# RF-INP-001.net
KiCad netlist of a schematic drawn in EAGLE
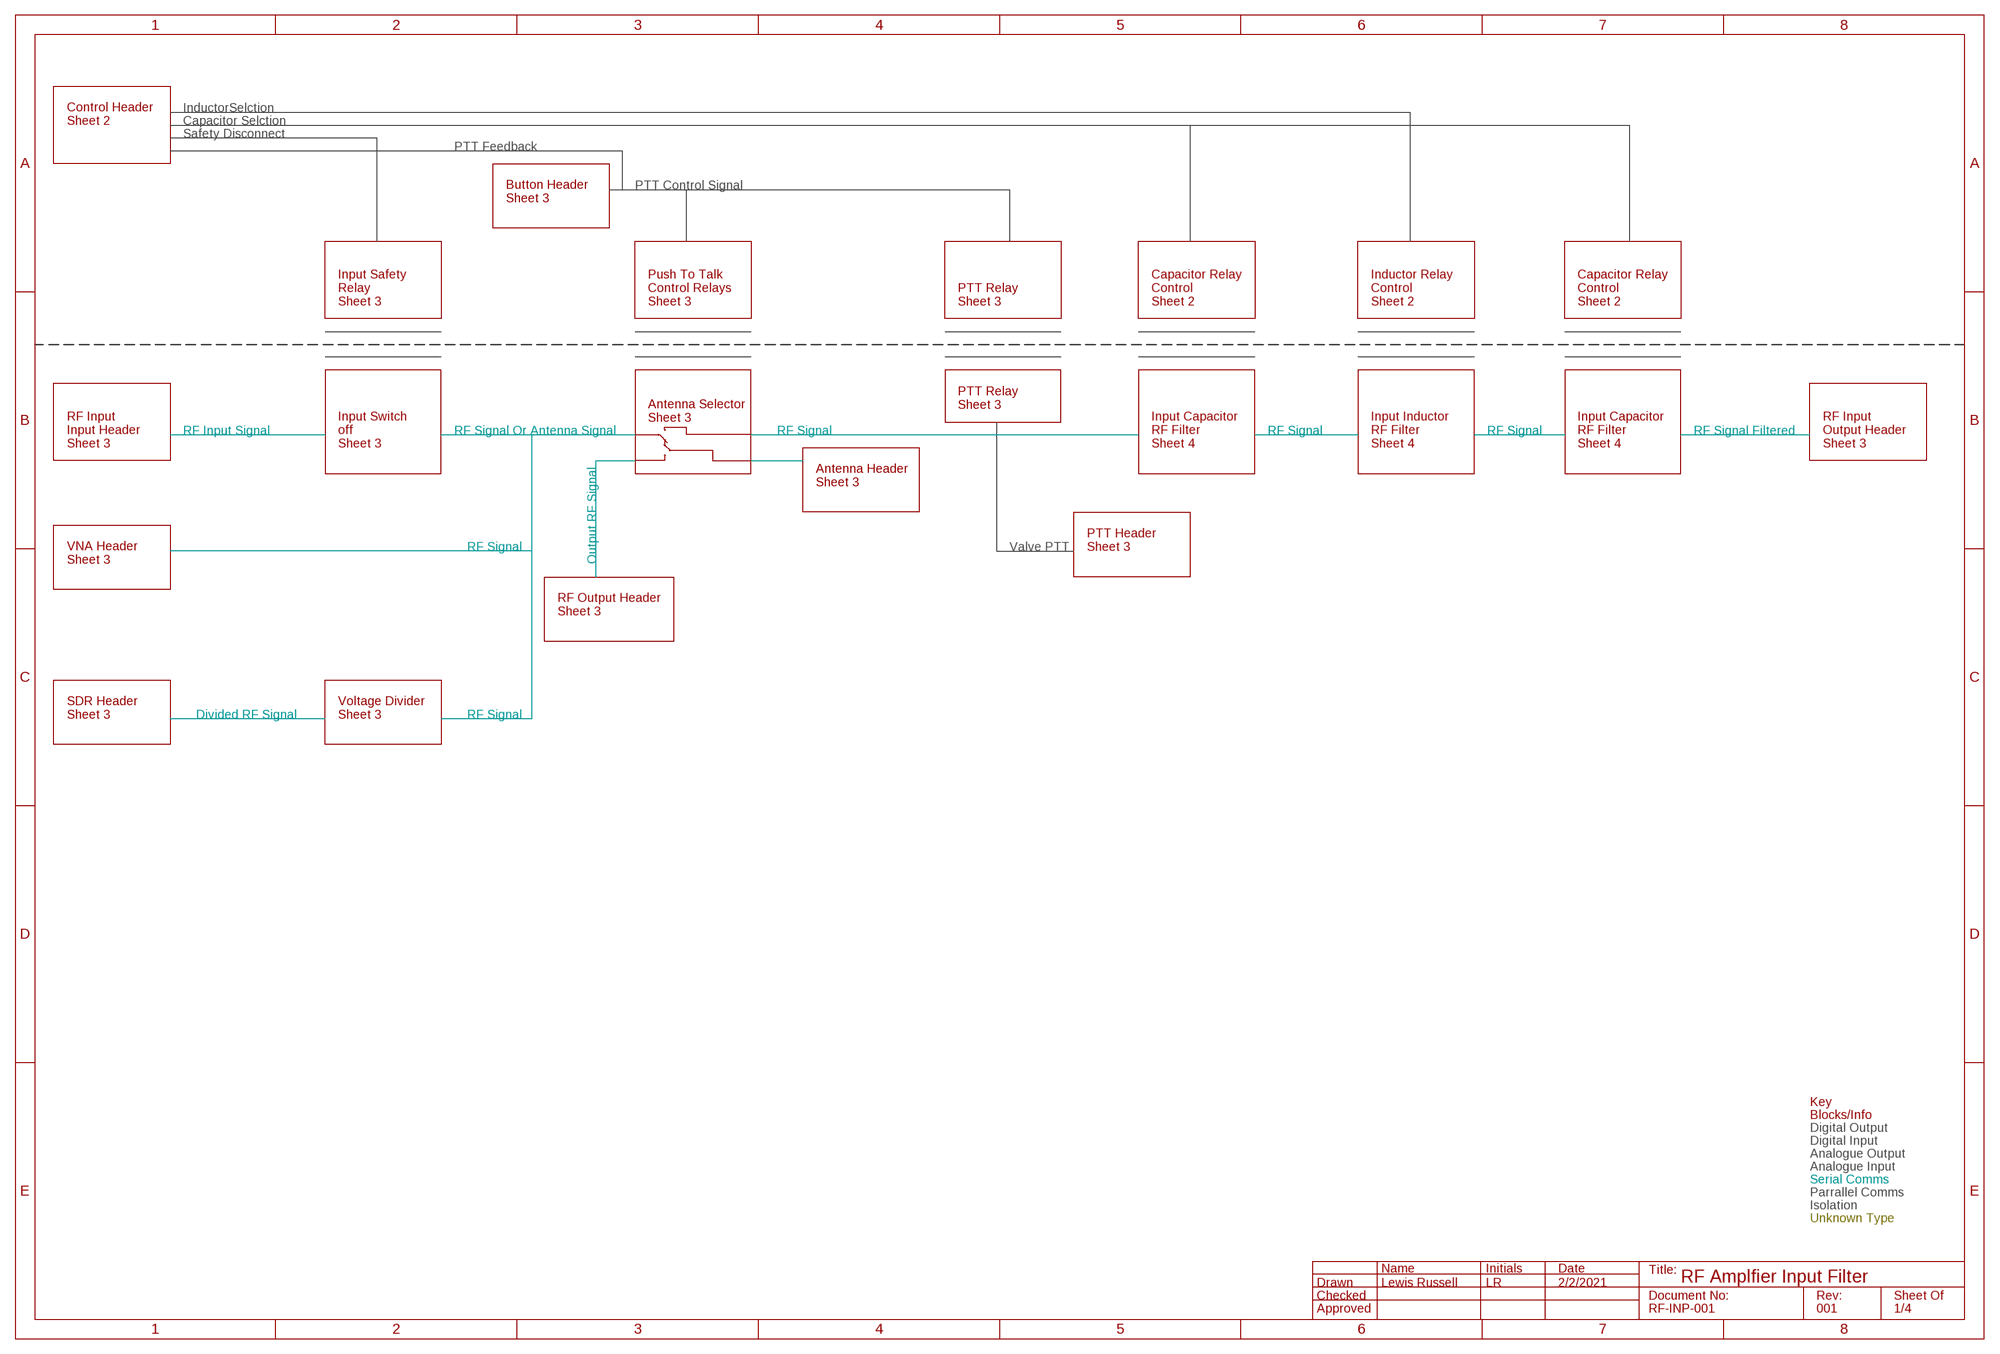
[diagram p0: schematic, sheet 1]
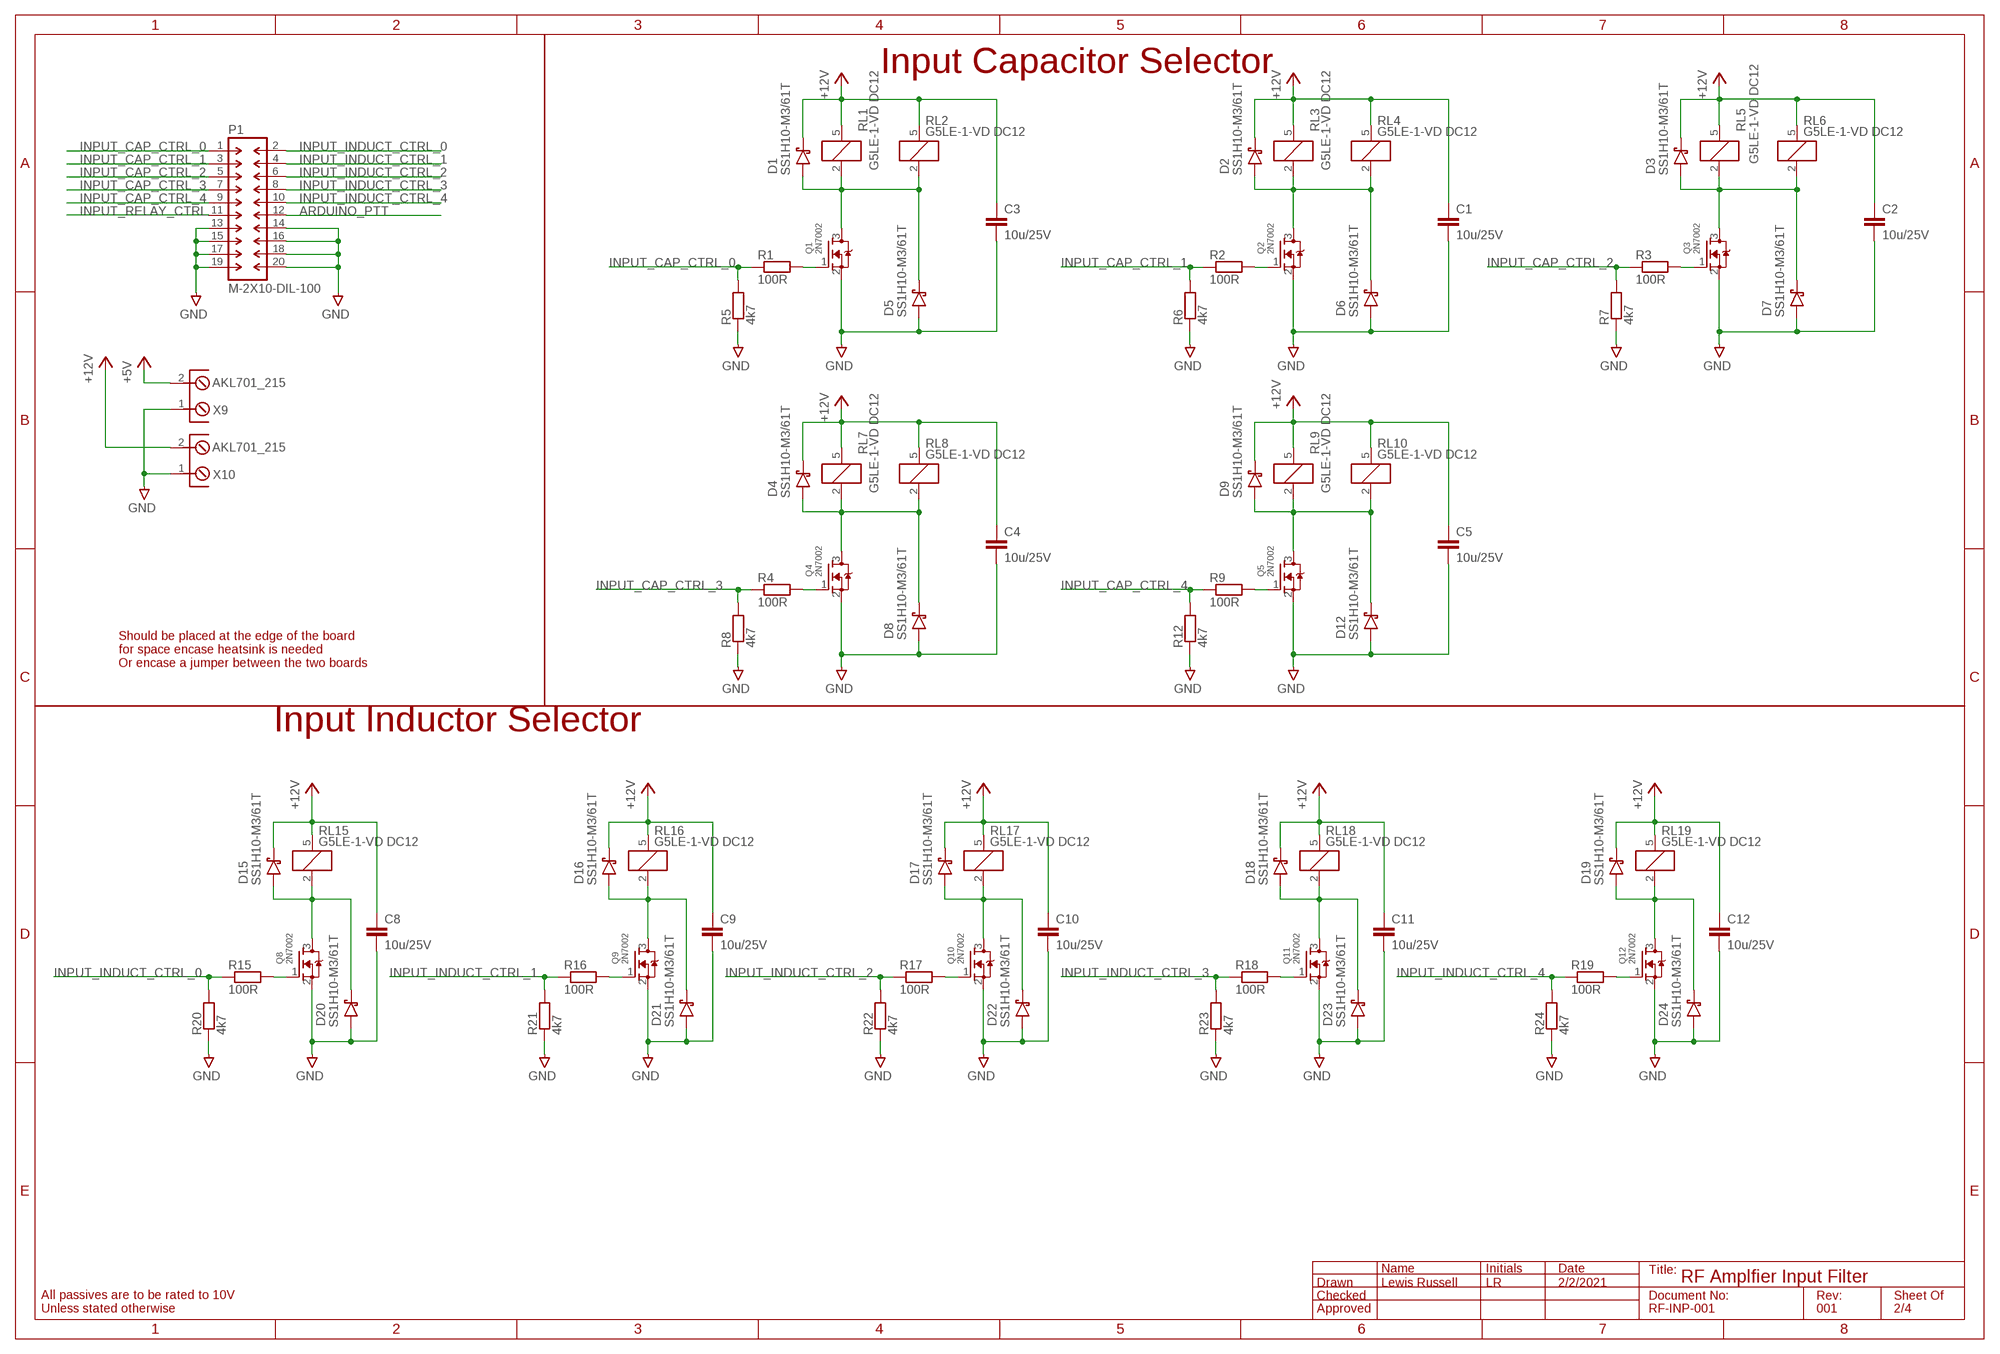
[diagram p1: schematic, sheet 2]
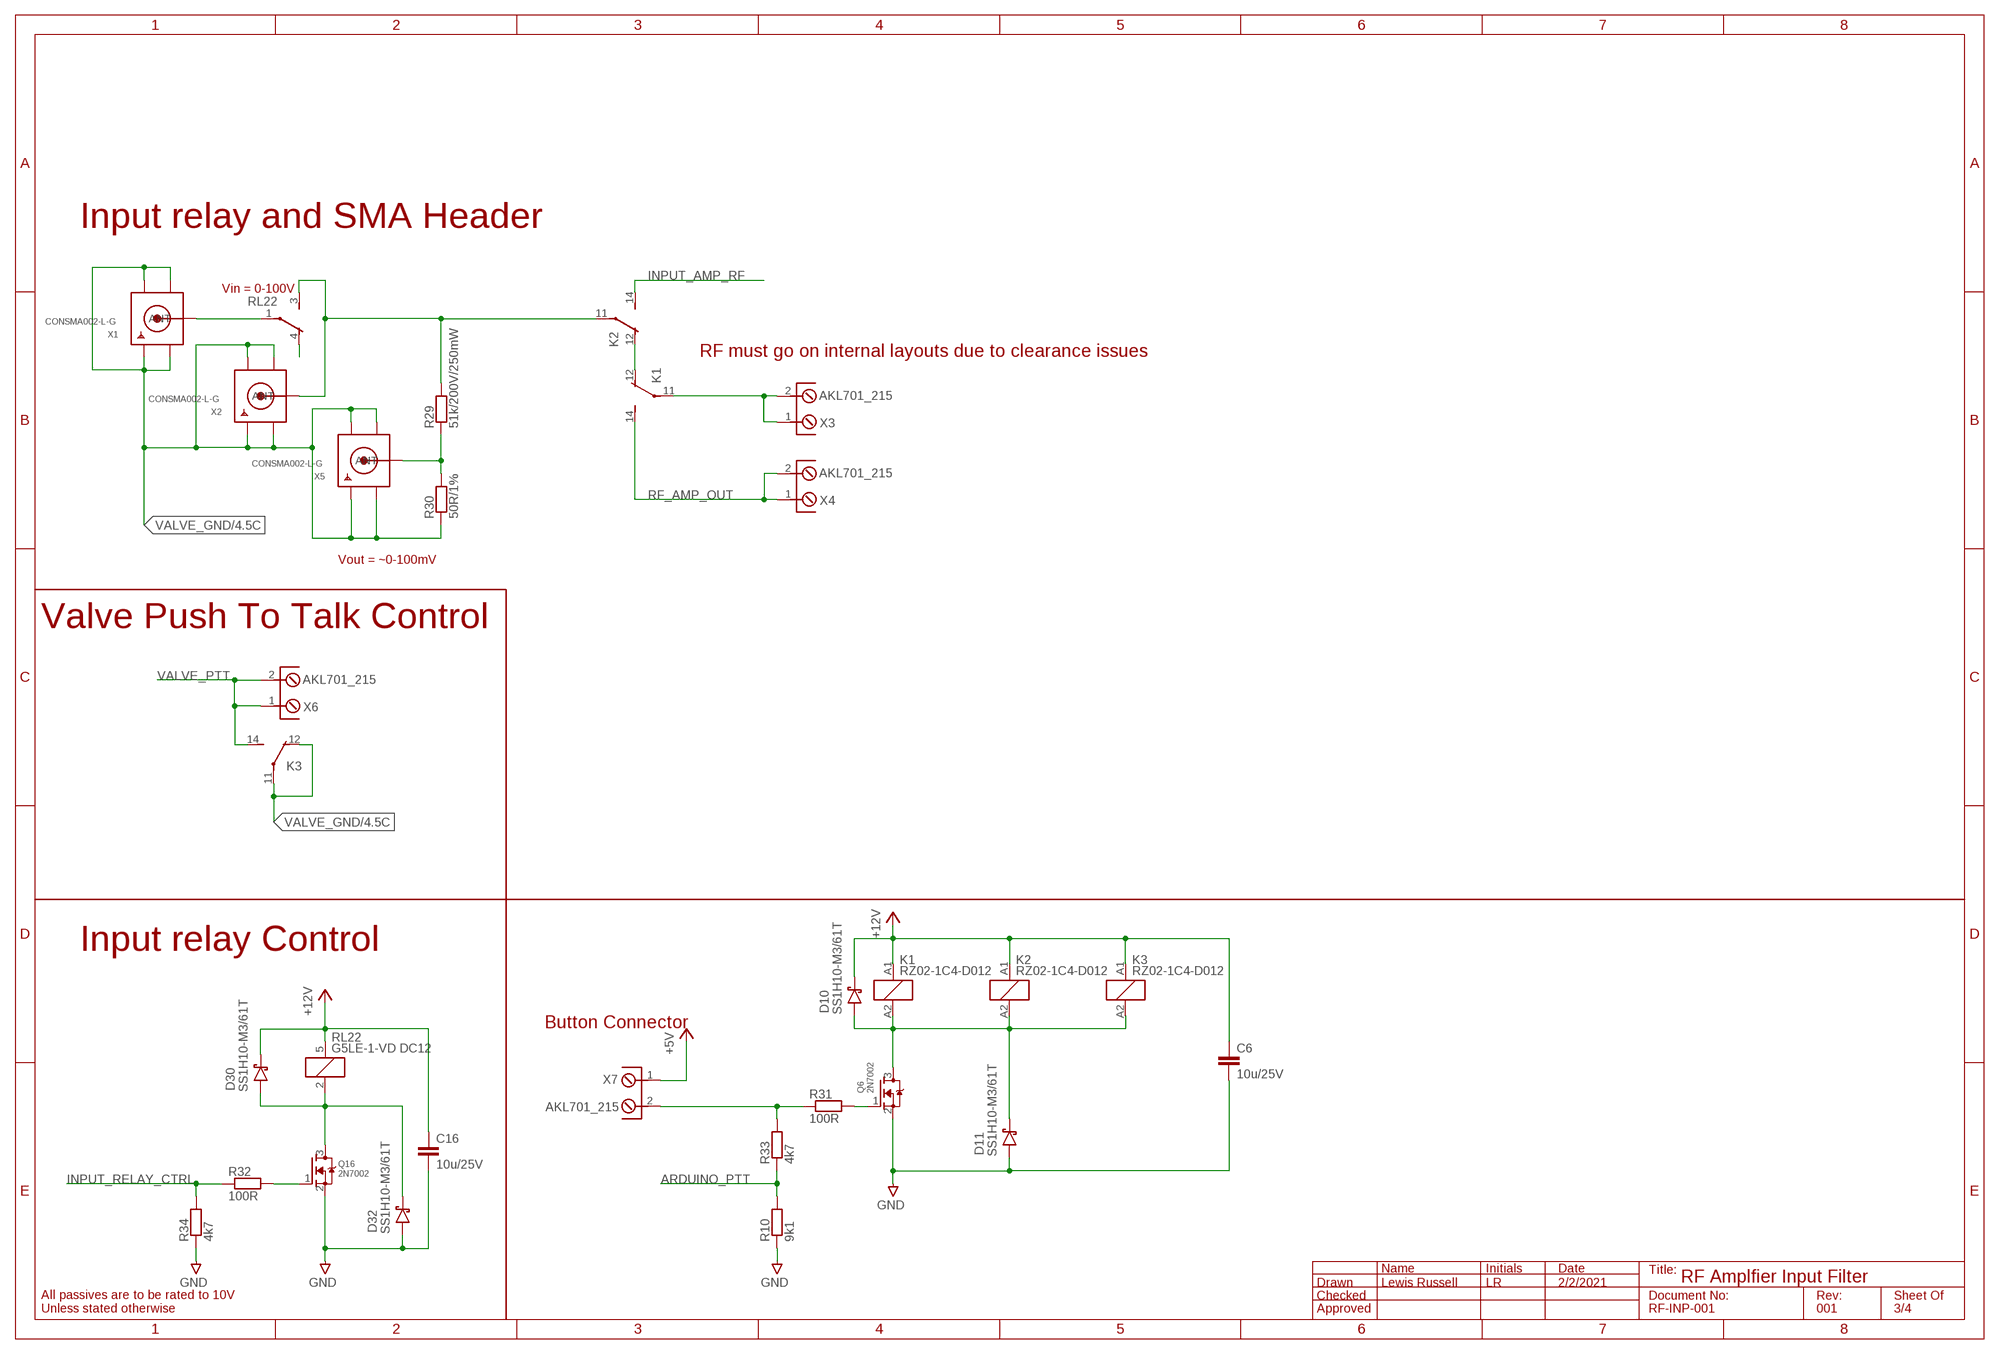
[diagram p2: schematic, sheet 3]
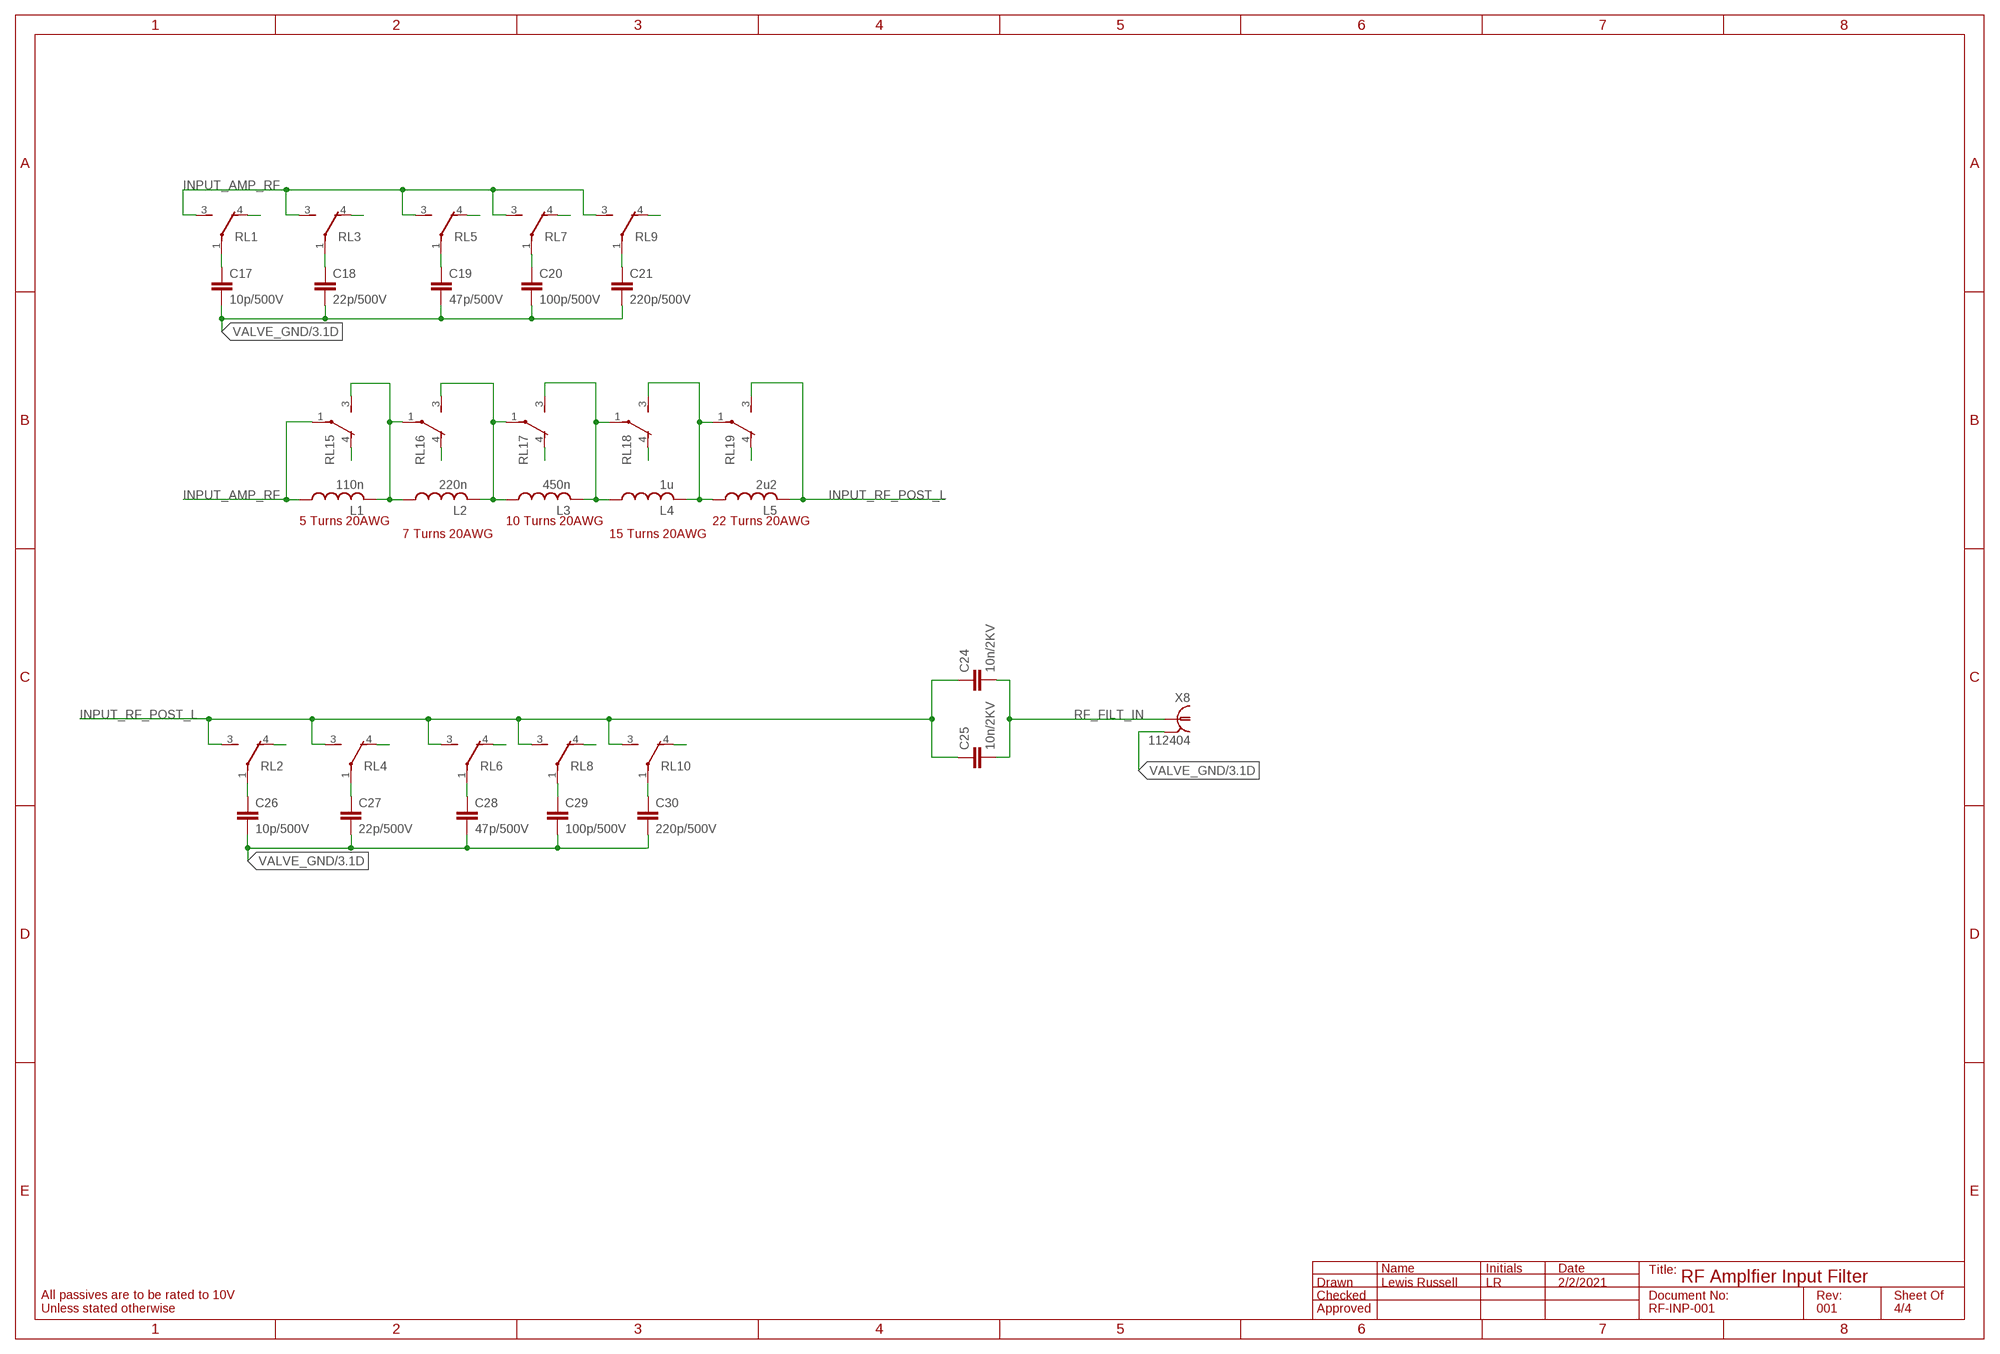
[diagram p3: schematic, sheet 4]

(export (version "E")
  (design (tool "Eeschema 10.0.6"))
  (components
    (comp (ref "C17")
      (value "10p/500V")
      (footprint "eagle-import:C1812")
      (libsource (lib "eagle-import") (part "C-EUC1812"))
    )
    (comp (ref "C18")
      (value "22p/500V")
      (footprint "eagle-import:C1812")
      (libsource (lib "eagle-import") (part "C-EUC1812"))
    )
    (comp (ref "C19")
      (value "47p/500V")
      (footprint "eagle-import:C1812")
      (libsource (lib "eagle-import") (part "C-EUC1812"))
    )
    (comp (ref "C20")
      (value "100p/500V")
      (footprint "eagle-import:C1812")
      (libsource (lib "eagle-import") (part "C-EUC1812"))
    )
    (comp (ref "C21")
      (value "220p/500V")
      (footprint "eagle-import:C1812")
      (libsource (lib "eagle-import") (part "C-EUC1812"))
    )
    (comp (ref "C24")
      (value "10n/2KV")
      (footprint "eagle-import:C1812")
      (libsource (lib "eagle-import") (part "C-EUC1812"))
    )
    (comp (ref "C25")
      (value "10n/2KV")
      (footprint "eagle-import:C1812")
      (libsource (lib "eagle-import") (part "C-EUC1812"))
    )
    (comp (ref "C26")
      (value "10p/500V")
      (footprint "eagle-import:C1812")
      (libsource (lib "eagle-import") (part "C-EUC1812"))
    )
    (comp (ref "C27")
      (value "22p/500V")
      (footprint "eagle-import:C1812")
      (libsource (lib "eagle-import") (part "C-EUC1812"))
    )
    (comp (ref "C28")
      (value "47p/500V")
      (footprint "eagle-import:C1812")
      (libsource (lib "eagle-import") (part "C-EUC1812"))
    )
    (comp (ref "C29")
      (value "100p/500V")
      (footprint "eagle-import:C1812")
      (libsource (lib "eagle-import") (part "C-EUC1812"))
    )
    (comp (ref "C30")
      (value "220p/500V")
      (footprint "eagle-import:C1812")
      (libsource (lib "eagle-import") (part "C-EUC1812"))
    )
    (comp (ref "L1")
      (value "110n")
      (footprint "eagle-import:T80-6")
      (libsource (lib "eagle-import") (part "T80-6"))
    )
    (comp (ref "L2")
      (value "220n")
      (footprint "eagle-import:T80-6")
      (libsource (lib "eagle-import") (part "T80-6"))
    )
    (comp (ref "L3")
      (value "450n")
      (footprint "eagle-import:T80-6")
      (libsource (lib "eagle-import") (part "T80-6"))
    )
    (comp (ref "L4")
      (value "1u")
      (footprint "eagle-import:T80-6")
      (libsource (lib "eagle-import") (part "T80-6"))
    )
    (comp (ref "L5")
      (value "2u2")
      (footprint "eagle-import:T80-6")
      (libsource (lib "eagle-import") (part "T80-6"))
    )
    (comp (ref "RL1")
      (value "G5LE-1-VD DC12")
      (footprint "eagle-import:SPDT")
      (libsource (lib "eagle-import") (part "G5LE-E"))
    )
    (comp (ref "RL2")
      (value "G5LE-1-VD DC12")
      (footprint "eagle-import:SPDT")
      (libsource (lib "eagle-import") (part "G5LE-E"))
    )
    (comp (ref "RL3")
      (value "G5LE-1-VD DC12")
      (footprint "eagle-import:SPDT")
      (libsource (lib "eagle-import") (part "G5LE-E"))
    )
    (comp (ref "RL4")
      (value "G5LE-1-VD DC12")
      (footprint "eagle-import:SPDT")
      (libsource (lib "eagle-import") (part "G5LE-E"))
    )
    (comp (ref "RL5")
      (value "G5LE-1-VD DC12")
      (footprint "eagle-import:SPDT")
      (libsource (lib "eagle-import") (part "G5LE-E"))
    )
    (comp (ref "RL6")
      (value "G5LE-1-VD DC12")
      (footprint "eagle-import:SPDT")
      (libsource (lib "eagle-import") (part "G5LE-E"))
    )
    (comp (ref "RL7")
      (value "G5LE-1-VD DC12")
      (footprint "eagle-import:SPDT")
      (libsource (lib "eagle-import") (part "G5LE-E"))
    )
    (comp (ref "RL8")
      (value "G5LE-1-VD DC12")
      (footprint "eagle-import:SPDT")
      (libsource (lib "eagle-import") (part "G5LE-E"))
    )
    (comp (ref "RL9")
      (value "G5LE-1-VD DC12")
      (footprint "eagle-import:SPDT")
      (libsource (lib "eagle-import") (part "G5LE-E"))
    )
    (comp (ref "RL10")
      (value "G5LE-1-VD DC12")
      (footprint "eagle-import:SPDT")
      (libsource (lib "eagle-import") (part "G5LE-E"))
    )
    (comp (ref "RL15")
      (value "G5LE-1-VD DC12")
      (footprint "eagle-import:SPDT")
      (libsource (lib "eagle-import") (part "G5LE-E"))
    )
    (comp (ref "RL16")
      (value "G5LE-1-VD DC12")
      (footprint "eagle-import:SPDT")
      (libsource (lib "eagle-import") (part "G5LE-E"))
    )
    (comp (ref "RL17")
      (value "G5LE-1-VD DC12")
      (footprint "eagle-import:SPDT")
      (libsource (lib "eagle-import") (part "G5LE-E"))
    )
    (comp (ref "RL18")
      (value "G5LE-1-VD DC12")
      (footprint "eagle-import:SPDT")
      (libsource (lib "eagle-import") (part "G5LE-E"))
    )
    (comp (ref "RL19")
      (value "G5LE-1-VD DC12")
      (footprint "eagle-import:SPDT")
      (libsource (lib "eagle-import") (part "G5LE-E"))
    )
    (comp (ref "X8")
      (value "112404")
      (footprint "eagle-import:112404")
      (fields (field (name "MF") "Amphenol Connex"))
      (libsource (lib "eagle-import") (part "112404"))
    )
    (comp (ref "C6")
      (value "10u/25V")
      (footprint "eagle-import:C0805")
      (libsource (lib "eagle-import") (part "C-EUC0805"))
    )
    (comp (ref "C16")
      (value "10u/25V")
      (footprint "eagle-import:C0805")
      (libsource (lib "eagle-import") (part "C-EUC0805"))
    )
    (comp (ref "D10")
      (value "SS1H10-M3/61T")
      (footprint "eagle-import:SMA_DO-214AC")
      (libsource (lib "eagle-import") (part "SCHOTTKY_DIODESMA"))
    )
    (comp (ref "D11")
      (value "SS1H10-M3/61T")
      (footprint "eagle-import:SMA_DO-214AC")
      (libsource (lib "eagle-import") (part "SCHOTTKY_DIODESMA"))
    )
    (comp (ref "D30")
      (value "SS1H10-M3/61T")
      (footprint "eagle-import:SMA_DO-214AC")
      (libsource (lib "eagle-import") (part "SCHOTTKY_DIODESMA"))
    )
    (comp (ref "D32")
      (value "SS1H10-M3/61T")
      (footprint "eagle-import:SMA_DO-214AC")
      (libsource (lib "eagle-import") (part "SCHOTTKY_DIODESMA"))
    )
    (comp (ref "K1")
      (value "RZ02-1C4-D012")
      (footprint "eagle-import:12A-5MM")
      (libsource (lib "eagle-import") (part "RZ02-1C"))
    )
    (comp (ref "K2")
      (value "RZ02-1C4-D012")
      (footprint "eagle-import:12A-5MM")
      (libsource (lib "eagle-import") (part "RZ02-1C"))
    )
    (comp (ref "K3")
      (value "RZ02-1C4-D012")
      (footprint "eagle-import:12A-5MM")
      (libsource (lib "eagle-import") (part "RZ02-1C"))
    )
    (comp (ref "Q6")
      (value "2N7002")
      (footprint "eagle-import:SOT23")
      (libsource (lib "eagle-import") (part "MOSFET-NREFLOW"))
    )
    (comp (ref "Q16")
      (value "2N7002")
      (footprint "eagle-import:SOT23")
      (libsource (lib "eagle-import") (part "MOSFET-NREFLOW"))
    )
    (comp (ref "R10")
      (value "9k1")
      (footprint "eagle-import:R0603")
      (libsource (lib "eagle-import") (part "R-EUR0603"))
    )
    (comp (ref "R29")
      (value "51k/200V/250mW")
      (footprint "eagle-import:R2512")
      (libsource (lib "eagle-import") (part "R-EUR2512"))
    )
    (comp (ref "R30")
      (value "50R/1%")
      (footprint "eagle-import:R0603")
      (libsource (lib "eagle-import") (part "R-EUR0603"))
    )
    (comp (ref "R31")
      (value "100R")
      (footprint "eagle-import:R0603")
      (libsource (lib "eagle-import") (part "R-EUR0603"))
    )
    (comp (ref "R32")
      (value "100R")
      (footprint "eagle-import:R0603")
      (libsource (lib "eagle-import") (part "R-EUR0603"))
    )
    (comp (ref "R33")
      (value "4k7")
      (footprint "eagle-import:R0603")
      (libsource (lib "eagle-import") (part "R-EUR0603"))
    )
    (comp (ref "R34")
      (value "4k7")
      (footprint "eagle-import:R0603")
      (libsource (lib "eagle-import") (part "R-EUR0603"))
    )
    (comp (ref "RL22")
      (value "G5LE-1-VD DC12")
      (footprint "eagle-import:SPDT")
      (libsource (lib "eagle-import") (part "G5LE-E"))
    )
    (comp (ref "X1")
      (value "CONSMA002-L-G")
      (footprint "eagle-import:SMA90_DIP")
      (libsource (lib "eagle-import") (part "SMACONNECTOR"))
    )
    (comp (ref "X2")
      (value "CONSMA002-L-G")
      (footprint "eagle-import:SMA90_DIP")
      (libsource (lib "eagle-import") (part "SMACONNECTOR"))
    )
    (comp (ref "X3")
      (value "AKL701_215")
      (footprint "eagle-import:AKL701_2_15")
      (libsource (lib "eagle-import") (part "AKL701_215"))
    )
    (comp (ref "X4")
      (value "AKL701_215")
      (footprint "eagle-import:AKL701_2_15")
      (libsource (lib "eagle-import") (part "AKL701_215"))
    )
    (comp (ref "X5")
      (value "CONSMA002-L-G")
      (footprint "eagle-import:SMA90_DIP")
      (libsource (lib "eagle-import") (part "SMACONNECTOR"))
    )
    (comp (ref "X6")
      (value "AKL701_215")
      (footprint "eagle-import:AKL701_2_15")
      (libsource (lib "eagle-import") (part "AKL701_215"))
    )
    (comp (ref "X7")
      (value "AKL701_215")
      (footprint "eagle-import:AKL701_2_15")
      (libsource (lib "eagle-import") (part "AKL701_215"))
    )
    (comp (ref "C1")
      (value "10u/25V")
      (footprint "eagle-import:C0805")
      (libsource (lib "eagle-import") (part "C-EUC0805"))
    )
    (comp (ref "C2")
      (value "10u/25V")
      (footprint "eagle-import:C0805")
      (libsource (lib "eagle-import") (part "C-EUC0805"))
    )
    (comp (ref "C3")
      (value "10u/25V")
      (footprint "eagle-import:C0805")
      (libsource (lib "eagle-import") (part "C-EUC0805"))
    )
    (comp (ref "C4")
      (value "10u/25V")
      (footprint "eagle-import:C0805")
      (libsource (lib "eagle-import") (part "C-EUC0805"))
    )
    (comp (ref "C5")
      (value "10u/25V")
      (footprint "eagle-import:C0805")
      (libsource (lib "eagle-import") (part "C-EUC0805"))
    )
    (comp (ref "C8")
      (value "10u/25V")
      (footprint "eagle-import:C0805")
      (libsource (lib "eagle-import") (part "C-EUC0805"))
    )
    (comp (ref "C9")
      (value "10u/25V")
      (footprint "eagle-import:C0805")
      (libsource (lib "eagle-import") (part "C-EUC0805"))
    )
    (comp (ref "C10")
      (value "10u/25V")
      (footprint "eagle-import:C0805")
      (libsource (lib "eagle-import") (part "C-EUC0805"))
    )
    (comp (ref "C11")
      (value "10u/25V")
      (footprint "eagle-import:C0805")
      (libsource (lib "eagle-import") (part "C-EUC0805"))
    )
    (comp (ref "C12")
      (value "10u/25V")
      (footprint "eagle-import:C0805")
      (libsource (lib "eagle-import") (part "C-EUC0805"))
    )
    (comp (ref "D1")
      (value "SS1H10-M3/61T")
      (footprint "eagle-import:SMA_DO-214AC")
      (libsource (lib "eagle-import") (part "SCHOTTKY_DIODESMA"))
    )
    (comp (ref "D2")
      (value "SS1H10-M3/61T")
      (footprint "eagle-import:SMA_DO-214AC")
      (libsource (lib "eagle-import") (part "SCHOTTKY_DIODESMA"))
    )
    (comp (ref "D3")
      (value "SS1H10-M3/61T")
      (footprint "eagle-import:SMA_DO-214AC")
      (libsource (lib "eagle-import") (part "SCHOTTKY_DIODESMA"))
    )
    (comp (ref "D4")
      (value "SS1H10-M3/61T")
      (footprint "eagle-import:SMA_DO-214AC")
      (libsource (lib "eagle-import") (part "SCHOTTKY_DIODESMA"))
    )
    (comp (ref "D5")
      (value "SS1H10-M3/61T")
      (footprint "eagle-import:SMA_DO-214AC")
      (libsource (lib "eagle-import") (part "SCHOTTKY_DIODESMA"))
    )
    (comp (ref "D6")
      (value "SS1H10-M3/61T")
      (footprint "eagle-import:SMA_DO-214AC")
      (libsource (lib "eagle-import") (part "SCHOTTKY_DIODESMA"))
    )
    (comp (ref "D7")
      (value "SS1H10-M3/61T")
      (footprint "eagle-import:SMA_DO-214AC")
      (libsource (lib "eagle-import") (part "SCHOTTKY_DIODESMA"))
    )
    (comp (ref "D8")
      (value "SS1H10-M3/61T")
      (footprint "eagle-import:SMA_DO-214AC")
      (libsource (lib "eagle-import") (part "SCHOTTKY_DIODESMA"))
    )
    (comp (ref "D9")
      (value "SS1H10-M3/61T")
      (footprint "eagle-import:SMA_DO-214AC")
      (libsource (lib "eagle-import") (part "SCHOTTKY_DIODESMA"))
    )
    (comp (ref "D12")
      (value "SS1H10-M3/61T")
      (footprint "eagle-import:SMA_DO-214AC")
      (libsource (lib "eagle-import") (part "SCHOTTKY_DIODESMA"))
    )
    (comp (ref "D15")
      (value "SS1H10-M3/61T")
      (footprint "eagle-import:SMA_DO-214AC")
      (libsource (lib "eagle-import") (part "SCHOTTKY_DIODESMA"))
    )
    (comp (ref "D16")
      (value "SS1H10-M3/61T")
      (footprint "eagle-import:SMA_DO-214AC")
      (libsource (lib "eagle-import") (part "SCHOTTKY_DIODESMA"))
    )
    (comp (ref "D17")
      (value "SS1H10-M3/61T")
      (footprint "eagle-import:SMA_DO-214AC")
      (libsource (lib "eagle-import") (part "SCHOTTKY_DIODESMA"))
    )
    (comp (ref "D18")
      (value "SS1H10-M3/61T")
      (footprint "eagle-import:SMA_DO-214AC")
      (libsource (lib "eagle-import") (part "SCHOTTKY_DIODESMA"))
    )
    (comp (ref "D19")
      (value "SS1H10-M3/61T")
      (footprint "eagle-import:SMA_DO-214AC")
      (libsource (lib "eagle-import") (part "SCHOTTKY_DIODESMA"))
    )
    (comp (ref "D20")
      (value "SS1H10-M3/61T")
      (footprint "eagle-import:SMA_DO-214AC")
      (libsource (lib "eagle-import") (part "SCHOTTKY_DIODESMA"))
    )
    (comp (ref "D21")
      (value "SS1H10-M3/61T")
      (footprint "eagle-import:SMA_DO-214AC")
      (libsource (lib "eagle-import") (part "SCHOTTKY_DIODESMA"))
    )
    (comp (ref "D22")
      (value "SS1H10-M3/61T")
      (footprint "eagle-import:SMA_DO-214AC")
      (libsource (lib "eagle-import") (part "SCHOTTKY_DIODESMA"))
    )
    (comp (ref "D23")
      (value "SS1H10-M3/61T")
      (footprint "eagle-import:SMA_DO-214AC")
      (libsource (lib "eagle-import") (part "SCHOTTKY_DIODESMA"))
    )
    (comp (ref "D24")
      (value "SS1H10-M3/61T")
      (footprint "eagle-import:SMA_DO-214AC")
      (libsource (lib "eagle-import") (part "SCHOTTKY_DIODESMA"))
    )
    (comp (ref "P1")
      (value "M-2X10-DIL-100")
      (footprint "eagle-import:DIL-100-2X10")
      (libsource (lib "eagle-import") (part "M-2X10-DIL-100"))
    )
    (comp (ref "Q1")
      (value "2N7002")
      (footprint "eagle-import:SOT23")
      (libsource (lib "eagle-import") (part "MOSFET-NREFLOW"))
    )
    (comp (ref "Q2")
      (value "2N7002")
      (footprint "eagle-import:SOT23")
      (libsource (lib "eagle-import") (part "MOSFET-NREFLOW"))
    )
    (comp (ref "Q3")
      (value "2N7002")
      (footprint "eagle-import:SOT23")
      (libsource (lib "eagle-import") (part "MOSFET-NREFLOW"))
    )
    (comp (ref "Q4")
      (value "2N7002")
      (footprint "eagle-import:SOT23")
      (libsource (lib "eagle-import") (part "MOSFET-NREFLOW"))
    )
    (comp (ref "Q5")
      (value "2N7002")
      (footprint "eagle-import:SOT23")
      (libsource (lib "eagle-import") (part "MOSFET-NREFLOW"))
    )
    (comp (ref "Q8")
      (value "2N7002")
      (footprint "eagle-import:SOT23")
      (libsource (lib "eagle-import") (part "MOSFET-NREFLOW"))
    )
    (comp (ref "Q9")
      (value "2N7002")
      (footprint "eagle-import:SOT23")
      (libsource (lib "eagle-import") (part "MOSFET-NREFLOW"))
    )
    (comp (ref "Q10")
      (value "2N7002")
      (footprint "eagle-import:SOT23")
      (libsource (lib "eagle-import") (part "MOSFET-NREFLOW"))
    )
    (comp (ref "Q11")
      (value "2N7002")
      (footprint "eagle-import:SOT23")
      (libsource (lib "eagle-import") (part "MOSFET-NREFLOW"))
    )
    (comp (ref "Q12")
      (value "2N7002")
      (footprint "eagle-import:SOT23")
      (libsource (lib "eagle-import") (part "MOSFET-NREFLOW"))
    )
    (comp (ref "R1")
      (value "100R")
      (footprint "eagle-import:R0603")
      (libsource (lib "eagle-import") (part "R-EUR0603"))
    )
    (comp (ref "R2")
      (value "100R")
      (footprint "eagle-import:R0603")
      (libsource (lib "eagle-import") (part "R-EUR0603"))
    )
    (comp (ref "R3")
      (value "100R")
      (footprint "eagle-import:R0603")
      (libsource (lib "eagle-import") (part "R-EUR0603"))
    )
    (comp (ref "R4")
      (value "100R")
      (footprint "eagle-import:R0603")
      (libsource (lib "eagle-import") (part "R-EUR0603"))
    )
    (comp (ref "R5")
      (value "4k7")
      (footprint "eagle-import:R0603")
      (libsource (lib "eagle-import") (part "R-EUR0603"))
    )
    (comp (ref "R6")
      (value "4k7")
      (footprint "eagle-import:R0603")
      (libsource (lib "eagle-import") (part "R-EUR0603"))
    )
    (comp (ref "R7")
      (value "4k7")
      (footprint "eagle-import:R0603")
      (libsource (lib "eagle-import") (part "R-EUR0603"))
    )
    (comp (ref "R8")
      (value "4k7")
      (footprint "eagle-import:R0603")
      (libsource (lib "eagle-import") (part "R-EUR0603"))
    )
    (comp (ref "R9")
      (value "100R")
      (footprint "eagle-import:R0603")
      (libsource (lib "eagle-import") (part "R-EUR0603"))
    )
    (comp (ref "R12")
      (value "4k7")
      (footprint "eagle-import:R0603")
      (libsource (lib "eagle-import") (part "R-EUR0603"))
    )
    (comp (ref "R15")
      (value "100R")
      (footprint "eagle-import:R0603")
      (libsource (lib "eagle-import") (part "R-EUR0603"))
    )
    (comp (ref "R16")
      (value "100R")
      (footprint "eagle-import:R0603")
      (libsource (lib "eagle-import") (part "R-EUR0603"))
    )
    (comp (ref "R17")
      (value "100R")
      (footprint "eagle-import:R0603")
      (libsource (lib "eagle-import") (part "R-EUR0603"))
    )
    (comp (ref "R18")
      (value "100R")
      (footprint "eagle-import:R0603")
      (libsource (lib "eagle-import") (part "R-EUR0603"))
    )
    (comp (ref "R19")
      (value "100R")
      (footprint "eagle-import:R0603")
      (libsource (lib "eagle-import") (part "R-EUR0603"))
    )
    (comp (ref "R20")
      (value "4k7")
      (footprint "eagle-import:R0603")
      (libsource (lib "eagle-import") (part "R-EUR0603"))
    )
    (comp (ref "R21")
      (value "4k7")
      (footprint "eagle-import:R0603")
      (libsource (lib "eagle-import") (part "R-EUR0603"))
    )
    (comp (ref "R22")
      (value "4k7")
      (footprint "eagle-import:R0603")
      (libsource (lib "eagle-import") (part "R-EUR0603"))
    )
    (comp (ref "R23")
      (value "4k7")
      (footprint "eagle-import:R0603")
      (libsource (lib "eagle-import") (part "R-EUR0603"))
    )
    (comp (ref "R24")
      (value "4k7")
      (footprint "eagle-import:R0603")
      (libsource (lib "eagle-import") (part "R-EUR0603"))
    )
    (comp (ref "X9")
      (value "AKL701_215")
      (footprint "eagle-import:AKL701_2_15")
      (libsource (lib "eagle-import") (part "AKL701_215"))
    )
    (comp (ref "X10")
      (value "AKL701_215")
      (footprint "eagle-import:AKL701_2_15")
      (libsource (lib "eagle-import") (part "AKL701_215"))
    )
  )
  (nets
    (net (code "1") (name "+5V") (class "Default")
      (node (ref "X7") (pin "1") (pinfunction "1_1") (pintype "passive"))
      (node (ref "X9") (pin "2") (pinfunction "2_2") (pintype "passive"))
    )
    (net (code "2") (name "+12V") (class "Default")
      (node (ref "C1") (pin "1") (pinfunction "1_1") (pintype "passive"))
      (node (ref "C10") (pin "1") (pinfunction "1_1") (pintype "passive"))
      (node (ref "C11") (pin "1") (pinfunction "1_1") (pintype "passive"))
      (node (ref "C12") (pin "1") (pinfunction "1_1") (pintype "passive"))
      (node (ref "C16") (pin "1") (pinfunction "1_1") (pintype "passive"))
      (node (ref "C2") (pin "1") (pinfunction "1_1") (pintype "passive"))
      (node (ref "C3") (pin "1") (pinfunction "1_1") (pintype "passive"))
      (node (ref "C4") (pin "1") (pinfunction "1_1") (pintype "passive"))
      (node (ref "C5") (pin "1") (pinfunction "1_1") (pintype "passive"))
      (node (ref "C6") (pin "1") (pinfunction "1_1") (pintype "passive"))
      (node (ref "C8") (pin "1") (pinfunction "1_1") (pintype "passive"))
      (node (ref "C9") (pin "1") (pinfunction "1_1") (pintype "passive"))
      (node (ref "D1") (pin "C") (pinfunction "CATHODE_C") (pintype "bidirectional"))
      (node (ref "D10") (pin "C") (pinfunction "CATHODE_C") (pintype "bidirectional"))
      (node (ref "D15") (pin "C") (pinfunction "CATHODE_C") (pintype "bidirectional"))
      (node (ref "D16") (pin "C") (pinfunction "CATHODE_C") (pintype "bidirectional"))
      (node (ref "D17") (pin "C") (pinfunction "CATHODE_C") (pintype "bidirectional"))
      (node (ref "D18") (pin "C") (pinfunction "CATHODE_C") (pintype "bidirectional"))
      (node (ref "D19") (pin "C") (pinfunction "CATHODE_C") (pintype "bidirectional"))
      (node (ref "D2") (pin "C") (pinfunction "CATHODE_C") (pintype "bidirectional"))
      (node (ref "D3") (pin "C") (pinfunction "CATHODE_C") (pintype "bidirectional"))
      (node (ref "D30") (pin "C") (pinfunction "CATHODE_C") (pintype "bidirectional"))
      (node (ref "D4") (pin "C") (pinfunction "CATHODE_C") (pintype "bidirectional"))
      (node (ref "D9") (pin "C") (pinfunction "CATHODE_C") (pintype "bidirectional"))
      (node (ref "K1") (pin "A1") (pinfunction "1_A1") (pintype "passive"))
      (node (ref "K2") (pin "A1") (pinfunction "1_A1") (pintype "passive"))
      (node (ref "K3") (pin "A1") (pinfunction "1_A1") (pintype "passive"))
      (node (ref "RL1") (pin "5") (pinfunction "5_5") (pintype "passive"))
      (node (ref "RL10") (pin "5") (pinfunction "5_5") (pintype "passive"))
      (node (ref "RL15") (pin "5") (pinfunction "5_5") (pintype "passive"))
      (node (ref "RL16") (pin "5") (pinfunction "5_5") (pintype "passive"))
      (node (ref "RL17") (pin "5") (pinfunction "5_5") (pintype "passive"))
      (node (ref "RL18") (pin "5") (pinfunction "5_5") (pintype "passive"))
      (node (ref "RL19") (pin "5") (pinfunction "5_5") (pintype "passive"))
      (node (ref "RL2") (pin "5") (pinfunction "5_5") (pintype "passive"))
      (node (ref "RL22") (pin "5") (pinfunction "5_5") (pintype "passive"))
      (node (ref "RL3") (pin "5") (pinfunction "5_5") (pintype "passive"))
      (node (ref "RL4") (pin "5") (pinfunction "5_5") (pintype "passive"))
      (node (ref "RL5") (pin "5") (pinfunction "5_5") (pintype "passive"))
      (node (ref "RL6") (pin "5") (pinfunction "5_5") (pintype "passive"))
      (node (ref "RL7") (pin "5") (pinfunction "5_5") (pintype "passive"))
      (node (ref "RL8") (pin "5") (pinfunction "5_5") (pintype "passive"))
      (node (ref "RL9") (pin "5") (pinfunction "5_5") (pintype "passive"))
      (node (ref "X10") (pin "2") (pinfunction "2_2") (pintype "passive"))
    )
    (net (code "3") (name "ARDUINO_PTT") (class "Default")
      (node (ref "P1") (pin "12") (pinfunction "12_12") (pintype "passive"))
      (node (ref "R10") (pin "2") (pinfunction "2_2") (pintype "passive"))
      (node (ref "R33") (pin "1") (pinfunction "1_1") (pintype "passive"))
    )
    (net (code "4") (name "GND") (class "Default")
      (node (ref "C1") (pin "2") (pinfunction "2_2") (pintype "passive"))
      (node (ref "C10") (pin "2") (pinfunction "2_2") (pintype "passive"))
      (node (ref "C11") (pin "2") (pinfunction "2_2") (pintype "passive"))
      (node (ref "C12") (pin "2") (pinfunction "2_2") (pintype "passive"))
      (node (ref "C16") (pin "2") (pinfunction "2_2") (pintype "passive"))
      (node (ref "C2") (pin "2") (pinfunction "2_2") (pintype "passive"))
      (node (ref "C3") (pin "2") (pinfunction "2_2") (pintype "passive"))
      (node (ref "C4") (pin "2") (pinfunction "2_2") (pintype "passive"))
      (node (ref "C5") (pin "2") (pinfunction "2_2") (pintype "passive"))
      (node (ref "C6") (pin "2") (pinfunction "2_2") (pintype "passive"))
      (node (ref "C8") (pin "2") (pinfunction "2_2") (pintype "passive"))
      (node (ref "C9") (pin "2") (pinfunction "2_2") (pintype "passive"))
      (node (ref "D11") (pin "A") (pinfunction "ANODE_A") (pintype "bidirectional"))
      (node (ref "D12") (pin "A") (pinfunction "ANODE_A") (pintype "bidirectional"))
      (node (ref "D20") (pin "A") (pinfunction "ANODE_A") (pintype "bidirectional"))
      (node (ref "D21") (pin "A") (pinfunction "ANODE_A") (pintype "bidirectional"))
      (node (ref "D22") (pin "A") (pinfunction "ANODE_A") (pintype "bidirectional"))
      (node (ref "D23") (pin "A") (pinfunction "ANODE_A") (pintype "bidirectional"))
      (node (ref "D24") (pin "A") (pinfunction "ANODE_A") (pintype "bidirectional"))
      (node (ref "D32") (pin "A") (pinfunction "ANODE_A") (pintype "bidirectional"))
      (node (ref "D5") (pin "A") (pinfunction "ANODE_A") (pintype "bidirectional"))
      (node (ref "D6") (pin "A") (pinfunction "ANODE_A") (pintype "bidirectional"))
      (node (ref "D7") (pin "A") (pinfunction "ANODE_A") (pintype "bidirectional"))
      (node (ref "D8") (pin "A") (pinfunction "ANODE_A") (pintype "bidirectional"))
      (node (ref "P1") (pin "13") (pinfunction "13_13") (pintype "passive"))
      (node (ref "P1") (pin "14") (pinfunction "14_14") (pintype "passive"))
      (node (ref "P1") (pin "15") (pinfunction "15_15") (pintype "passive"))
      (node (ref "P1") (pin "16") (pinfunction "16_16") (pintype "passive"))
      (node (ref "P1") (pin "17") (pinfunction "17_17") (pintype "passive"))
      (node (ref "P1") (pin "18") (pinfunction "18_18") (pintype "passive"))
      (node (ref "P1") (pin "19") (pinfunction "19_19") (pintype "passive"))
      (node (ref "P1") (pin "20") (pinfunction "20_20") (pintype "passive"))
      (node (ref "Q1") (pin "2") (pinfunction "S_2") (pintype "bidirectional"))
      (node (ref "Q10") (pin "2") (pinfunction "S_2") (pintype "bidirectional"))
      (node (ref "Q11") (pin "2") (pinfunction "S_2") (pintype "bidirectional"))
      (node (ref "Q12") (pin "2") (pinfunction "S_2") (pintype "bidirectional"))
      (node (ref "Q16") (pin "2") (pinfunction "S_2") (pintype "bidirectional"))
      (node (ref "Q2") (pin "2") (pinfunction "S_2") (pintype "bidirectional"))
      (node (ref "Q3") (pin "2") (pinfunction "S_2") (pintype "bidirectional"))
      (node (ref "Q4") (pin "2") (pinfunction "S_2") (pintype "bidirectional"))
      (node (ref "Q5") (pin "2") (pinfunction "S_2") (pintype "bidirectional"))
      (node (ref "Q6") (pin "2") (pinfunction "S_2") (pintype "bidirectional"))
      (node (ref "Q8") (pin "2") (pinfunction "S_2") (pintype "bidirectional"))
      (node (ref "Q9") (pin "2") (pinfunction "S_2") (pintype "bidirectional"))
      (node (ref "R10") (pin "1") (pinfunction "1_1") (pintype "passive"))
      (node (ref "R12") (pin "1") (pinfunction "1_1") (pintype "passive"))
      (node (ref "R20") (pin "1") (pinfunction "1_1") (pintype "passive"))
      (node (ref "R21") (pin "1") (pinfunction "1_1") (pintype "passive"))
      (node (ref "R22") (pin "1") (pinfunction "1_1") (pintype "passive"))
      (node (ref "R23") (pin "1") (pinfunction "1_1") (pintype "passive"))
      (node (ref "R24") (pin "1") (pinfunction "1_1") (pintype "passive"))
      (node (ref "R34") (pin "1") (pinfunction "1_1") (pintype "passive"))
      (node (ref "R5") (pin "1") (pinfunction "1_1") (pintype "passive"))
      (node (ref "R6") (pin "1") (pinfunction "1_1") (pintype "passive"))
      (node (ref "R7") (pin "1") (pinfunction "1_1") (pintype "passive"))
      (node (ref "R8") (pin "1") (pinfunction "1_1") (pintype "passive"))
      (node (ref "X10") (pin "1") (pinfunction "1_1") (pintype "passive"))
      (node (ref "X9") (pin "1") (pinfunction "1_1") (pintype "passive"))
    )
    (net (code "5") (name "INPUT_AMP_RF") (class "Default")
      (node (ref "K2") (pin "14") (pinfunction "NO_14") (pintype "passive"))
      (node (ref "L1") (pin "1") (pinfunction "1_1") (pintype "passive"))
      (node (ref "RL1") (pin "3") (pinfunction "3_3") (pintype "passive"))
      (node (ref "RL15") (pin "1") (pinfunction "1_1") (pintype "passive"))
      (node (ref "RL3") (pin "3") (pinfunction "3_3") (pintype "passive"))
      (node (ref "RL5") (pin "3") (pinfunction "3_3") (pintype "passive"))
      (node (ref "RL7") (pin "3") (pinfunction "3_3") (pintype "passive"))
      (node (ref "RL9") (pin "3") (pinfunction "3_3") (pintype "passive"))
    )
    (net (code "6") (name "INPUT_CAP_CTRL_0") (class "Default")
      (node (ref "P1") (pin "1") (pinfunction "1_1") (pintype "passive"))
      (node (ref "R1") (pin "1") (pinfunction "1_1") (pintype "passive"))
      (node (ref "R5") (pin "2") (pinfunction "2_2") (pintype "passive"))
    )
    (net (code "7") (name "INPUT_CAP_CTRL_1") (class "Default")
      (node (ref "P1") (pin "3") (pinfunction "3_3") (pintype "passive"))
      (node (ref "R2") (pin "1") (pinfunction "1_1") (pintype "passive"))
      (node (ref "R6") (pin "2") (pinfunction "2_2") (pintype "passive"))
    )
    (net (code "8") (name "INPUT_CAP_CTRL_2") (class "Default")
      (node (ref "P1") (pin "5") (pinfunction "5_5") (pintype "passive"))
      (node (ref "R3") (pin "1") (pinfunction "1_1") (pintype "passive"))
      (node (ref "R7") (pin "2") (pinfunction "2_2") (pintype "passive"))
    )
    (net (code "9") (name "INPUT_CAP_CTRL_3") (class "Default")
      (node (ref "P1") (pin "7") (pinfunction "7_7") (pintype "passive"))
      (node (ref "R4") (pin "1") (pinfunction "1_1") (pintype "passive"))
      (node (ref "R8") (pin "2") (pinfunction "2_2") (pintype "passive"))
    )
    (net (code "10") (name "INPUT_CAP_CTRL_4") (class "Default")
      (node (ref "P1") (pin "9") (pinfunction "9_9") (pintype "passive"))
      (node (ref "R12") (pin "2") (pinfunction "2_2") (pintype "passive"))
      (node (ref "R9") (pin "1") (pinfunction "1_1") (pintype "passive"))
    )
    (net (code "11") (name "INPUT_INDUCT_CTRL_0") (class "Default")
      (node (ref "P1") (pin "2") (pinfunction "2_2") (pintype "passive"))
      (node (ref "R15") (pin "1") (pinfunction "1_1") (pintype "passive"))
      (node (ref "R20") (pin "2") (pinfunction "2_2") (pintype "passive"))
    )
    (net (code "12") (name "INPUT_INDUCT_CTRL_1") (class "Default")
      (node (ref "P1") (pin "4") (pinfunction "4_4") (pintype "passive"))
      (node (ref "R16") (pin "1") (pinfunction "1_1") (pintype "passive"))
      (node (ref "R21") (pin "2") (pinfunction "2_2") (pintype "passive"))
    )
    (net (code "13") (name "INPUT_INDUCT_CTRL_2") (class "Default")
      (node (ref "P1") (pin "6") (pinfunction "6_6") (pintype "passive"))
      (node (ref "R17") (pin "1") (pinfunction "1_1") (pintype "passive"))
      (node (ref "R22") (pin "2") (pinfunction "2_2") (pintype "passive"))
    )
    (net (code "14") (name "INPUT_INDUCT_CTRL_3") (class "Default")
      (node (ref "P1") (pin "8") (pinfunction "8_8") (pintype "passive"))
      (node (ref "R18") (pin "1") (pinfunction "1_1") (pintype "passive"))
      (node (ref "R23") (pin "2") (pinfunction "2_2") (pintype "passive"))
    )
    (net (code "15") (name "INPUT_INDUCT_CTRL_4") (class "Default")
      (node (ref "P1") (pin "10") (pinfunction "10_10") (pintype "passive"))
      (node (ref "R19") (pin "1") (pinfunction "1_1") (pintype "passive"))
      (node (ref "R24") (pin "2") (pinfunction "2_2") (pintype "passive"))
    )
    (net (code "16") (name "INPUT_RELAY_CTRL") (class "Default")
      (node (ref "P1") (pin "11") (pinfunction "11_11") (pintype "passive"))
      (node (ref "R32") (pin "1") (pinfunction "1_1") (pintype "passive"))
      (node (ref "R34") (pin "2") (pinfunction "2_2") (pintype "passive"))
    )
    (net (code "17") (name "INPUT_RF_POST_L") (class "Default")
      (node (ref "C24") (pin "1") (pinfunction "1_1") (pintype "passive"))
      (node (ref "C25") (pin "1") (pinfunction "1_1") (pintype "passive"))
      (node (ref "L5") (pin "2") (pinfunction "2_2") (pintype "passive"))
      (node (ref "RL10") (pin "3") (pinfunction "3_3") (pintype "passive"))
      (node (ref "RL19") (pin "3") (pinfunction "3_3") (pintype "passive"))
      (node (ref "RL2") (pin "3") (pinfunction "3_3") (pintype "passive"))
      (node (ref "RL4") (pin "3") (pinfunction "3_3") (pintype "passive"))
      (node (ref "RL6") (pin "3") (pinfunction "3_3") (pintype "passive"))
      (node (ref "RL8") (pin "3") (pinfunction "3_3") (pintype "passive"))
    )
    (net (code "18") (name "Net-(C17-Pad1)") (class "Default")
      (node (ref "C17") (pin "1") (pinfunction "1_1") (pintype "passive"))
      (node (ref "RL1") (pin "1") (pinfunction "1_1") (pintype "passive"))
    )
    (net (code "19") (name "Net-(C18-Pad1)") (class "Default")
      (node (ref "C18") (pin "1") (pinfunction "1_1") (pintype "passive"))
      (node (ref "RL3") (pin "1") (pinfunction "1_1") (pintype "passive"))
    )
    (net (code "20") (name "Net-(C19-Pad1)") (class "Default")
      (node (ref "C19") (pin "1") (pinfunction "1_1") (pintype "passive"))
      (node (ref "RL5") (pin "1") (pinfunction "1_1") (pintype "passive"))
    )
    (net (code "21") (name "Net-(C20-Pad1)") (class "Default")
      (node (ref "C20") (pin "1") (pinfunction "1_1") (pintype "passive"))
      (node (ref "RL7") (pin "1") (pinfunction "1_1") (pintype "passive"))
    )
    (net (code "22") (name "Net-(C21-Pad1)") (class "Default")
      (node (ref "C21") (pin "1") (pinfunction "1_1") (pintype "passive"))
      (node (ref "RL9") (pin "1") (pinfunction "1_1") (pintype "passive"))
    )
    (net (code "23") (name "Net-(C26-Pad1)") (class "Default")
      (node (ref "C26") (pin "1") (pinfunction "1_1") (pintype "passive"))
      (node (ref "RL2") (pin "1") (pinfunction "1_1") (pintype "passive"))
    )
    (net (code "24") (name "Net-(C27-Pad1)") (class "Default")
      (node (ref "C27") (pin "1") (pinfunction "1_1") (pintype "passive"))
      (node (ref "RL4") (pin "1") (pinfunction "1_1") (pintype "passive"))
    )
    (net (code "25") (name "Net-(C28-Pad1)") (class "Default")
      (node (ref "C28") (pin "1") (pinfunction "1_1") (pintype "passive"))
      (node (ref "RL6") (pin "1") (pinfunction "1_1") (pintype "passive"))
    )
    (net (code "26") (name "Net-(C29-Pad1)") (class "Default")
      (node (ref "C29") (pin "1") (pinfunction "1_1") (pintype "passive"))
      (node (ref "RL8") (pin "1") (pinfunction "1_1") (pintype "passive"))
    )
    (net (code "27") (name "Net-(C30-Pad1)") (class "Default")
      (node (ref "C30") (pin "1") (pinfunction "1_1") (pintype "passive"))
      (node (ref "RL10") (pin "1") (pinfunction "1_1") (pintype "passive"))
    )
    (net (code "28") (name "Net-(D1-ANODE)") (class "Default")
      (node (ref "D1") (pin "A") (pinfunction "ANODE_A") (pintype "bidirectional"))
      (node (ref "D5") (pin "C") (pinfunction "CATHODE_C") (pintype "bidirectional"))
      (node (ref "Q1") (pin "3") (pinfunction "D_3") (pintype "bidirectional"))
      (node (ref "RL1") (pin "2") (pinfunction "2_2") (pintype "passive"))
      (node (ref "RL2") (pin "2") (pinfunction "2_2") (pintype "passive"))
    )
    (net (code "29") (name "Net-(D2-ANODE)") (class "Default")
      (node (ref "D2") (pin "A") (pinfunction "ANODE_A") (pintype "bidirectional"))
      (node (ref "D6") (pin "C") (pinfunction "CATHODE_C") (pintype "bidirectional"))
      (node (ref "Q2") (pin "3") (pinfunction "D_3") (pintype "bidirectional"))
      (node (ref "RL3") (pin "2") (pinfunction "2_2") (pintype "passive"))
      (node (ref "RL4") (pin "2") (pinfunction "2_2") (pintype "passive"))
    )
    (net (code "30") (name "Net-(D3-ANODE)") (class "Default")
      (node (ref "D3") (pin "A") (pinfunction "ANODE_A") (pintype "bidirectional"))
      (node (ref "D7") (pin "C") (pinfunction "CATHODE_C") (pintype "bidirectional"))
      (node (ref "Q3") (pin "3") (pinfunction "D_3") (pintype "bidirectional"))
      (node (ref "RL5") (pin "2") (pinfunction "2_2") (pintype "passive"))
      (node (ref "RL6") (pin "2") (pinfunction "2_2") (pintype "passive"))
    )
    (net (code "31") (name "Net-(D4-ANODE)") (class "Default")
      (node (ref "D4") (pin "A") (pinfunction "ANODE_A") (pintype "bidirectional"))
      (node (ref "D8") (pin "C") (pinfunction "CATHODE_C") (pintype "bidirectional"))
      (node (ref "Q4") (pin "3") (pinfunction "D_3") (pintype "bidirectional"))
      (node (ref "RL7") (pin "2") (pinfunction "2_2") (pintype "passive"))
      (node (ref "RL8") (pin "2") (pinfunction "2_2") (pintype "passive"))
    )
    (net (code "32") (name "Net-(D10-ANODE)") (class "Default")
      (node (ref "D10") (pin "A") (pinfunction "ANODE_A") (pintype "bidirectional"))
      (node (ref "D11") (pin "C") (pinfunction "CATHODE_C") (pintype "bidirectional"))
      (node (ref "K1") (pin "A2") (pinfunction "2_A2") (pintype "passive"))
      (node (ref "K2") (pin "A2") (pinfunction "2_A2") (pintype "passive"))
      (node (ref "K3") (pin "A2") (pinfunction "2_A2") (pintype "passive"))
      (node (ref "Q6") (pin "3") (pinfunction "D_3") (pintype "bidirectional"))
    )
    (net (code "33") (name "Net-(D12-CATHODE)") (class "Default")
      (node (ref "D12") (pin "C") (pinfunction "CATHODE_C") (pintype "bidirectional"))
      (node (ref "D9") (pin "A") (pinfunction "ANODE_A") (pintype "bidirectional"))
      (node (ref "Q5") (pin "3") (pinfunction "D_3") (pintype "bidirectional"))
      (node (ref "RL10") (pin "2") (pinfunction "2_2") (pintype "passive"))
      (node (ref "RL9") (pin "2") (pinfunction "2_2") (pintype "passive"))
    )
    (net (code "34") (name "Net-(D15-ANODE)") (class "Default")
      (node (ref "D15") (pin "A") (pinfunction "ANODE_A") (pintype "bidirectional"))
      (node (ref "D20") (pin "C") (pinfunction "CATHODE_C") (pintype "bidirectional"))
      (node (ref "Q8") (pin "3") (pinfunction "D_3") (pintype "bidirectional"))
      (node (ref "RL15") (pin "2") (pinfunction "2_2") (pintype "passive"))
    )
    (net (code "35") (name "Net-(D16-ANODE)") (class "Default")
      (node (ref "D16") (pin "A") (pinfunction "ANODE_A") (pintype "bidirectional"))
      (node (ref "D21") (pin "C") (pinfunction "CATHODE_C") (pintype "bidirectional"))
      (node (ref "Q9") (pin "3") (pinfunction "D_3") (pintype "bidirectional"))
      (node (ref "RL16") (pin "2") (pinfunction "2_2") (pintype "passive"))
    )
    (net (code "36") (name "Net-(D17-ANODE)") (class "Default")
      (node (ref "D17") (pin "A") (pinfunction "ANODE_A") (pintype "bidirectional"))
      (node (ref "D22") (pin "C") (pinfunction "CATHODE_C") (pintype "bidirectional"))
      (node (ref "Q10") (pin "3") (pinfunction "D_3") (pintype "bidirectional"))
      (node (ref "RL17") (pin "2") (pinfunction "2_2") (pintype "passive"))
    )
    (net (code "37") (name "Net-(D18-ANODE)") (class "Default")
      (node (ref "D18") (pin "A") (pinfunction "ANODE_A") (pintype "bidirectional"))
      (node (ref "D23") (pin "C") (pinfunction "CATHODE_C") (pintype "bidirectional"))
      (node (ref "Q11") (pin "3") (pinfunction "D_3") (pintype "bidirectional"))
      (node (ref "RL18") (pin "2") (pinfunction "2_2") (pintype "passive"))
    )
    (net (code "38") (name "Net-(D19-ANODE)") (class "Default")
      (node (ref "D19") (pin "A") (pinfunction "ANODE_A") (pintype "bidirectional"))
      (node (ref "D24") (pin "C") (pinfunction "CATHODE_C") (pintype "bidirectional"))
      (node (ref "Q12") (pin "3") (pinfunction "D_3") (pintype "bidirectional"))
      (node (ref "RL19") (pin "2") (pinfunction "2_2") (pintype "passive"))
    )
    (net (code "39") (name "Net-(D30-ANODE)") (class "Default")
      (node (ref "D30") (pin "A") (pinfunction "ANODE_A") (pintype "bidirectional"))
      (node (ref "D32") (pin "C") (pinfunction "CATHODE_C") (pintype "bidirectional"))
      (node (ref "Q16") (pin "3") (pinfunction "D_3") (pintype "bidirectional"))
      (node (ref "RL22") (pin "2") (pinfunction "2_2") (pintype "passive"))
    )
    (net (code "40") (name "Net-(K1B-COM)") (class "Default")
      (node (ref "K1") (pin "11") (pinfunction "COM_11") (pintype "passive"))
      (node (ref "X3") (pin "1") (pinfunction "1_1") (pintype "passive"))
      (node (ref "X3") (pin "2") (pinfunction "2_2") (pintype "passive"))
    )
    (net (code "41") (name "Net-(K1B-NC)") (class "Default")
      (node (ref "K1") (pin "12") (pinfunction "NC_12") (pintype "passive"))
      (node (ref "K2") (pin "12") (pinfunction "NC_12") (pintype "passive"))
    )
    (net (code "42") (name "Net-(K2B-COM)") (class "Default")
      (node (ref "K2") (pin "11") (pinfunction "COM_11") (pintype "passive"))
      (node (ref "R29") (pin "2") (pinfunction "2_2") (pintype "passive"))
      (node (ref "RL22") (pin "3") (pinfunction "3_3") (pintype "passive"))
      (node (ref "X2") (pin "ANTENNA") (pinfunction "ANT_ANTENNA") (pintype "bidirectional"))
    )
    (net (code "43") (name "Net-(L1-Pad2)") (class "Default")
      (node (ref "L1") (pin "2") (pinfunction "2_2") (pintype "passive"))
      (node (ref "L2") (pin "1") (pinfunction "1_1") (pintype "passive"))
      (node (ref "RL15") (pin "3") (pinfunction "3_3") (pintype "passive"))
      (node (ref "RL16") (pin "1") (pinfunction "1_1") (pintype "passive"))
    )
    (net (code "44") (name "Net-(L2-Pad2)") (class "Default")
      (node (ref "L2") (pin "2") (pinfunction "2_2") (pintype "passive"))
      (node (ref "L3") (pin "1") (pinfunction "1_1") (pintype "passive"))
      (node (ref "RL16") (pin "3") (pinfunction "3_3") (pintype "passive"))
      (node (ref "RL17") (pin "1") (pinfunction "1_1") (pintype "passive"))
    )
    (net (code "45") (name "Net-(L3-Pad2)") (class "Default")
      (node (ref "L3") (pin "2") (pinfunction "2_2") (pintype "passive"))
      (node (ref "L4") (pin "1") (pinfunction "1_1") (pintype "passive"))
      (node (ref "RL17") (pin "3") (pinfunction "3_3") (pintype "passive"))
      (node (ref "RL18") (pin "1") (pinfunction "1_1") (pintype "passive"))
    )
    (net (code "46") (name "Net-(L4-Pad2)") (class "Default")
      (node (ref "L4") (pin "2") (pinfunction "2_2") (pintype "passive"))
      (node (ref "L5") (pin "1") (pinfunction "1_1") (pintype "passive"))
      (node (ref "RL18") (pin "3") (pinfunction "3_3") (pintype "passive"))
      (node (ref "RL19") (pin "1") (pinfunction "1_1") (pintype "passive"))
    )
    (net (code "47") (name "Net-(Q1-G)") (class "Default")
      (node (ref "Q1") (pin "1") (pinfunction "G_1") (pintype "bidirectional"))
      (node (ref "R1") (pin "2") (pinfunction "2_2") (pintype "passive"))
    )
    (net (code "48") (name "Net-(Q2-G)") (class "Default")
      (node (ref "Q2") (pin "1") (pinfunction "G_1") (pintype "bidirectional"))
      (node (ref "R2") (pin "2") (pinfunction "2_2") (pintype "passive"))
    )
    (net (code "49") (name "Net-(Q3-G)") (class "Default")
      (node (ref "Q3") (pin "1") (pinfunction "G_1") (pintype "bidirectional"))
      (node (ref "R3") (pin "2") (pinfunction "2_2") (pintype "passive"))
    )
    (net (code "50") (name "Net-(Q4-G)") (class "Default")
      (node (ref "Q4") (pin "1") (pinfunction "G_1") (pintype "bidirectional"))
      (node (ref "R4") (pin "2") (pinfunction "2_2") (pintype "passive"))
    )
    (net (code "51") (name "Net-(Q5-G)") (class "Default")
      (node (ref "Q5") (pin "1") (pinfunction "G_1") (pintype "bidirectional"))
      (node (ref "R9") (pin "2") (pinfunction "2_2") (pintype "passive"))
    )
    (net (code "52") (name "Net-(Q6-G)") (class "Default")
      (node (ref "Q6") (pin "1") (pinfunction "G_1") (pintype "bidirectional"))
      (node (ref "R31") (pin "2") (pinfunction "2_2") (pintype "passive"))
    )
    (net (code "53") (name "Net-(Q8-G)") (class "Default")
      (node (ref "Q8") (pin "1") (pinfunction "G_1") (pintype "bidirectional"))
      (node (ref "R15") (pin "2") (pinfunction "2_2") (pintype "passive"))
    )
    (net (code "54") (name "Net-(Q9-G)") (class "Default")
      (node (ref "Q9") (pin "1") (pinfunction "G_1") (pintype "bidirectional"))
      (node (ref "R16") (pin "2") (pinfunction "2_2") (pintype "passive"))
    )
    (net (code "55") (name "Net-(Q10-G)") (class "Default")
      (node (ref "Q10") (pin "1") (pinfunction "G_1") (pintype "bidirectional"))
      (node (ref "R17") (pin "2") (pinfunction "2_2") (pintype "passive"))
    )
    (net (code "56") (name "Net-(Q11-G)") (class "Default")
      (node (ref "Q11") (pin "1") (pinfunction "G_1") (pintype "bidirectional"))
      (node (ref "R18") (pin "2") (pinfunction "2_2") (pintype "passive"))
    )
    (net (code "57") (name "Net-(Q12-G)") (class "Default")
      (node (ref "Q12") (pin "1") (pinfunction "G_1") (pintype "bidirectional"))
      (node (ref "R19") (pin "2") (pinfunction "2_2") (pintype "passive"))
    )
    (net (code "58") (name "Net-(Q16-G)") (class "Default")
      (node (ref "Q16") (pin "1") (pinfunction "G_1") (pintype "bidirectional"))
      (node (ref "R32") (pin "2") (pinfunction "2_2") (pintype "passive"))
    )
    (net (code "59") (name "Net-(R31-Pad1)") (class "Default")
      (node (ref "R31") (pin "1") (pinfunction "1_1") (pintype "passive"))
      (node (ref "R33") (pin "2") (pinfunction "2_2") (pintype "passive"))
      (node (ref "X7") (pin "2") (pinfunction "2_2") (pintype "passive"))
    )
    (net (code "60") (name "Net-(X1-ANT)") (class "Default")
      (node (ref "RL22") (pin "1") (pinfunction "1_1") (pintype "passive"))
      (node (ref "X1") (pin "ANTENNA") (pinfunction "ANT_ANTENNA") (pintype "bidirectional"))
    )
    (net (code "61") (name "Net-(X5-ANT)") (class "Default")
      (node (ref "R29") (pin "1") (pinfunction "1_1") (pintype "passive"))
      (node (ref "R30") (pin "2") (pinfunction "2_2") (pintype "passive"))
      (node (ref "X5") (pin "ANTENNA") (pinfunction "ANT_ANTENNA") (pintype "bidirectional"))
    )
    (net (code "62") (name "RF_AMP_OUT") (class "Default")
      (node (ref "K1") (pin "14") (pinfunction "NO_14") (pintype "passive"))
      (node (ref "X4") (pin "1") (pinfunction "1_1") (pintype "passive"))
      (node (ref "X4") (pin "2") (pinfunction "2_2") (pintype "passive"))
    )
    (net (code "63") (name "RF_FILT_IN") (class "Default")
      (node (ref "C24") (pin "2") (pinfunction "2_2") (pintype "passive"))
      (node (ref "C25") (pin "2") (pinfunction "2_2") (pintype "passive"))
      (node (ref "X8") (pin "1") (pinfunction "1_1") (pintype "passive"))
    )
    (net (code "64") (name "VALVE_GND") (class "Default")
      (node (ref "C17") (pin "2") (pinfunction "2_2") (pintype "passive"))
      (node (ref "C18") (pin "2") (pinfunction "2_2") (pintype "passive"))
      (node (ref "C19") (pin "2") (pinfunction "2_2") (pintype "passive"))
      (node (ref "C20") (pin "2") (pinfunction "2_2") (pintype "passive"))
      (node (ref "C21") (pin "2") (pinfunction "2_2") (pintype "passive"))
      (node (ref "C26") (pin "2") (pinfunction "2_2") (pintype "passive"))
      (node (ref "C27") (pin "2") (pinfunction "2_2") (pintype "passive"))
      (node (ref "C28") (pin "2") (pinfunction "2_2") (pintype "passive"))
      (node (ref "C29") (pin "2") (pinfunction "2_2") (pintype "passive"))
      (node (ref "C30") (pin "2") (pinfunction "2_2") (pintype "passive"))
      (node (ref "K3") (pin "11") (pinfunction "COM_11") (pintype "passive"))
      (node (ref "K3") (pin "12") (pinfunction "NC_12") (pintype "passive"))
      (node (ref "R30") (pin "1") (pinfunction "1_1") (pintype "passive"))
      (node (ref "X1") (pin "GND1") (pinfunction "GND1_GND1") (pintype "power_in"))
      (node (ref "X1") (pin "GND2") (pinfunction "GND2_GND2") (pintype "power_in"))
      (node (ref "X1") (pin "GND3") (pinfunction "GND3_GND3") (pintype "power_in"))
      (node (ref "X1") (pin "GND4") (pinfunction "GND4_GND4") (pintype "power_in"))
      (node (ref "X2") (pin "GND1") (pinfunction "GND1_GND1") (pintype "power_in"))
      (node (ref "X2") (pin "GND2") (pinfunction "GND2_GND2") (pintype "power_in"))
      (node (ref "X2") (pin "GND3") (pinfunction "GND3_GND3") (pintype "power_in"))
      (node (ref "X2") (pin "GND4") (pinfunction "GND4_GND4") (pintype "power_in"))
      (node (ref "X5") (pin "GND1") (pinfunction "GND1_GND1") (pintype "power_in"))
      (node (ref "X5") (pin "GND2") (pinfunction "GND2_GND2") (pintype "power_in"))
      (node (ref "X5") (pin "GND3") (pinfunction "GND3_GND3") (pintype "power_in"))
      (node (ref "X5") (pin "GND4") (pinfunction "GND4_GND4") (pintype "power_in"))
      (node (ref "X8") (pin "2") (pinfunction "2_2") (pintype "passive"))
      (node (ref "X8") (pin "3") (pinfunction "2_3") (pintype "passive"))
      (node (ref "X8") (pin "4") (pinfunction "2_4") (pintype "passive"))
      (node (ref "X8") (pin "5") (pinfunction "2_5") (pintype "passive"))
    )
    (net (code "65") (name "VALVE_PTT") (class "Default")
      (node (ref "K3") (pin "14") (pinfunction "NO_14") (pintype "passive"))
      (node (ref "X6") (pin "1") (pinfunction "1_1") (pintype "passive"))
      (node (ref "X6") (pin "2") (pinfunction "2_2") (pintype "passive"))
    )
    (net (code "66") (name "unconnected-(RL1-Pad4)") (class "Default")
      (node (ref "RL1") (pin "4") (pinfunction "4_4") (pintype "passive"))
    )
    (net (code "67") (name "unconnected-(RL2-Pad4)") (class "Default")
      (node (ref "RL2") (pin "4") (pinfunction "4_4") (pintype "passive"))
    )
    (net (code "68") (name "unconnected-(RL3-Pad4)") (class "Default")
      (node (ref "RL3") (pin "4") (pinfunction "4_4") (pintype "passive"))
    )
    (net (code "69") (name "unconnected-(RL4-Pad4)") (class "Default")
      (node (ref "RL4") (pin "4") (pinfunction "4_4") (pintype "passive"))
    )
    (net (code "70") (name "unconnected-(RL5-Pad4)") (class "Default")
      (node (ref "RL5") (pin "4") (pinfunction "4_4") (pintype "passive"))
    )
    (net (code "71") (name "unconnected-(RL6-Pad4)") (class "Default")
      (node (ref "RL6") (pin "4") (pinfunction "4_4") (pintype "passive"))
    )
    (net (code "72") (name "unconnected-(RL7-Pad4)") (class "Default")
      (node (ref "RL7") (pin "4") (pinfunction "4_4") (pintype "passive"))
    )
    (net (code "73") (name "unconnected-(RL8-Pad4)") (class "Default")
      (node (ref "RL8") (pin "4") (pinfunction "4_4") (pintype "passive"))
    )
    (net (code "74") (name "unconnected-(RL9-Pad4)") (class "Default")
      (node (ref "RL9") (pin "4") (pinfunction "4_4") (pintype "passive"))
    )
    (net (code "75") (name "unconnected-(RL10-Pad4)") (class "Default")
      (node (ref "RL10") (pin "4") (pinfunction "4_4") (pintype "passive"))
    )
    (net (code "76") (name "unconnected-(RL15-Pad4)") (class "Default")
      (node (ref "RL15") (pin "4") (pinfunction "4_4") (pintype "passive"))
    )
    (net (code "77") (name "unconnected-(RL16-Pad4)") (class "Default")
      (node (ref "RL16") (pin "4") (pinfunction "4_4") (pintype "passive"))
    )
    (net (code "78") (name "unconnected-(RL17-Pad4)") (class "Default")
      (node (ref "RL17") (pin "4") (pinfunction "4_4") (pintype "passive"))
    )
    (net (code "79") (name "unconnected-(RL18-Pad4)") (class "Default")
      (node (ref "RL18") (pin "4") (pinfunction "4_4") (pintype "passive"))
    )
    (net (code "80") (name "unconnected-(RL19-Pad4)") (class "Default")
      (node (ref "RL19") (pin "4") (pinfunction "4_4") (pintype "passive"))
    )
    (net (code "81") (name "unconnected-(RL22-Pad4)") (class "Default")
      (node (ref "RL22") (pin "4") (pinfunction "4_4") (pintype "passive"))
    )
  )
)
